# Current_Sense.net
KiCad netlist of a schematic drawn in Altium Designer
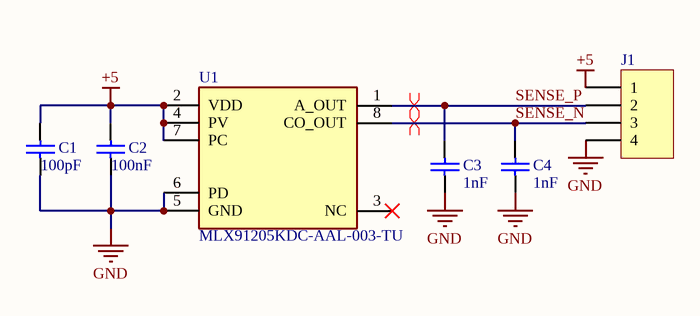
[diagram p0: Current Sense.SchDoc]

(export (version "E")
  (design (tool "Eeschema 10.0.6"))
  (components
    (comp (ref "C1")
      (value "100pF")
      (footprint "0402")
      (description "Capacitor")
      (fields (field (name "Comment") "Cap") (field (name "PUBLISHER") "Altium Limited"))
      (libsource (lib "Miscellaneous Devices") (part "Cap"))
    )
    (comp (ref "C2")
      (value "100nF")
      (footprint "0402")
      (description "Capacitor")
      (fields (field (name "Comment") "Cap") (field (name "PUBLISHER") "Altium Limited"))
      (libsource (lib "Miscellaneous Devices") (part "Cap"))
    )
    (comp (ref "C3")
      (value "1nF")
      (footprint "0402")
      (description "Capacitor")
      (fields (field (name "Comment") "Cap") (field (name "PUBLISHER") "Altium Limited"))
      (libsource (lib "Miscellaneous Devices") (part "Cap"))
    )
    (comp (ref "C4")
      (value "1nF")
      (footprint "0402")
      (description "Capacitor")
      (fields (field (name "Comment") "Cap") (field (name "PUBLISHER") "Altium Limited"))
      (libsource (lib "Miscellaneous Devices") (part "Cap"))
    )
    (comp (ref "J1")
      (value "Header 4H")
      (footprint "HDR1X4")
      (description "Header, 4-Pin, Right Angle")
      (fields (field (name "PUBLISHER") "Altium Limited"))
      (libsource (lib "Miscellaneous Connectors") (part "Header 4H"))
    )
    (comp (ref "U1")
      (value "MLX91205KDC-AAL-003-TU")
      (footprint "SOIC127P602X173-8N")
      (description "Integrated Circuit")
      (fields (field (name "MOUSER PART NUMBER") "482-91205KDCAAL003TU"))
      (libsource (lib "Motor Controller") (part "MLX91205KDC-AAL-003-TU"))
    )
  )
  (nets
    (net (code "1") (name "+5") (class "Default")
      (node (ref "C1") (pin "2") (pinfunction "2_2") (pintype "passive"))
      (node (ref "C2") (pin "2") (pinfunction "2_2") (pintype "passive"))
      (node (ref "J1") (pin "1") (pinfunction "1_1") (pintype "passive"))
      (node (ref "U1") (pin "2") (pinfunction "VDD_2") (pintype "passive"))
      (node (ref "U1") (pin "4") (pinfunction "PV_4") (pintype "passive"))
      (node (ref "U1") (pin "7") (pinfunction "PC_7") (pintype "passive"))
    )
    (net (code "2") (name "/SENSE_N") (class "Default")
      (node (ref "C4") (pin "2") (pinfunction "2_2") (pintype "passive"))
      (node (ref "J1") (pin "3") (pinfunction "3_3") (pintype "passive"))
      (node (ref "U1") (pin "8") (pinfunction "CO_OUT_8") (pintype "passive"))
    )
    (net (code "3") (name "/SENSE_P") (class "Default")
      (node (ref "C3") (pin "2") (pinfunction "2_2") (pintype "passive"))
      (node (ref "J1") (pin "2") (pinfunction "2_2") (pintype "passive"))
      (node (ref "U1") (pin "1") (pinfunction "A_OUT_1") (pintype "passive"))
    )
    (net (code "4") (name "GND") (class "Default")
      (node (ref "C1") (pin "1") (pinfunction "1_1") (pintype "passive"))
      (node (ref "C2") (pin "1") (pinfunction "1_1") (pintype "passive"))
      (node (ref "C3") (pin "1") (pinfunction "1_1") (pintype "passive"))
      (node (ref "C4") (pin "1") (pinfunction "1_1") (pintype "passive"))
      (node (ref "J1") (pin "4") (pinfunction "4_4") (pintype "passive"))
      (node (ref "U1") (pin "5") (pinfunction "GND_5") (pintype "passive"))
      (node (ref "U1") (pin "6") (pinfunction "PD_6") (pintype "passive"))
    )
    (net (code "5") (name "unconnected-(U1-NC-Pad3)") (class "Default")
      (node (ref "U1") (pin "3") (pinfunction "NC_3") (pintype "passive+no_connect"))
    )
  )
)
